# PowerSupply.net
KiCad netlist of a schematic drawn in Altium Designer
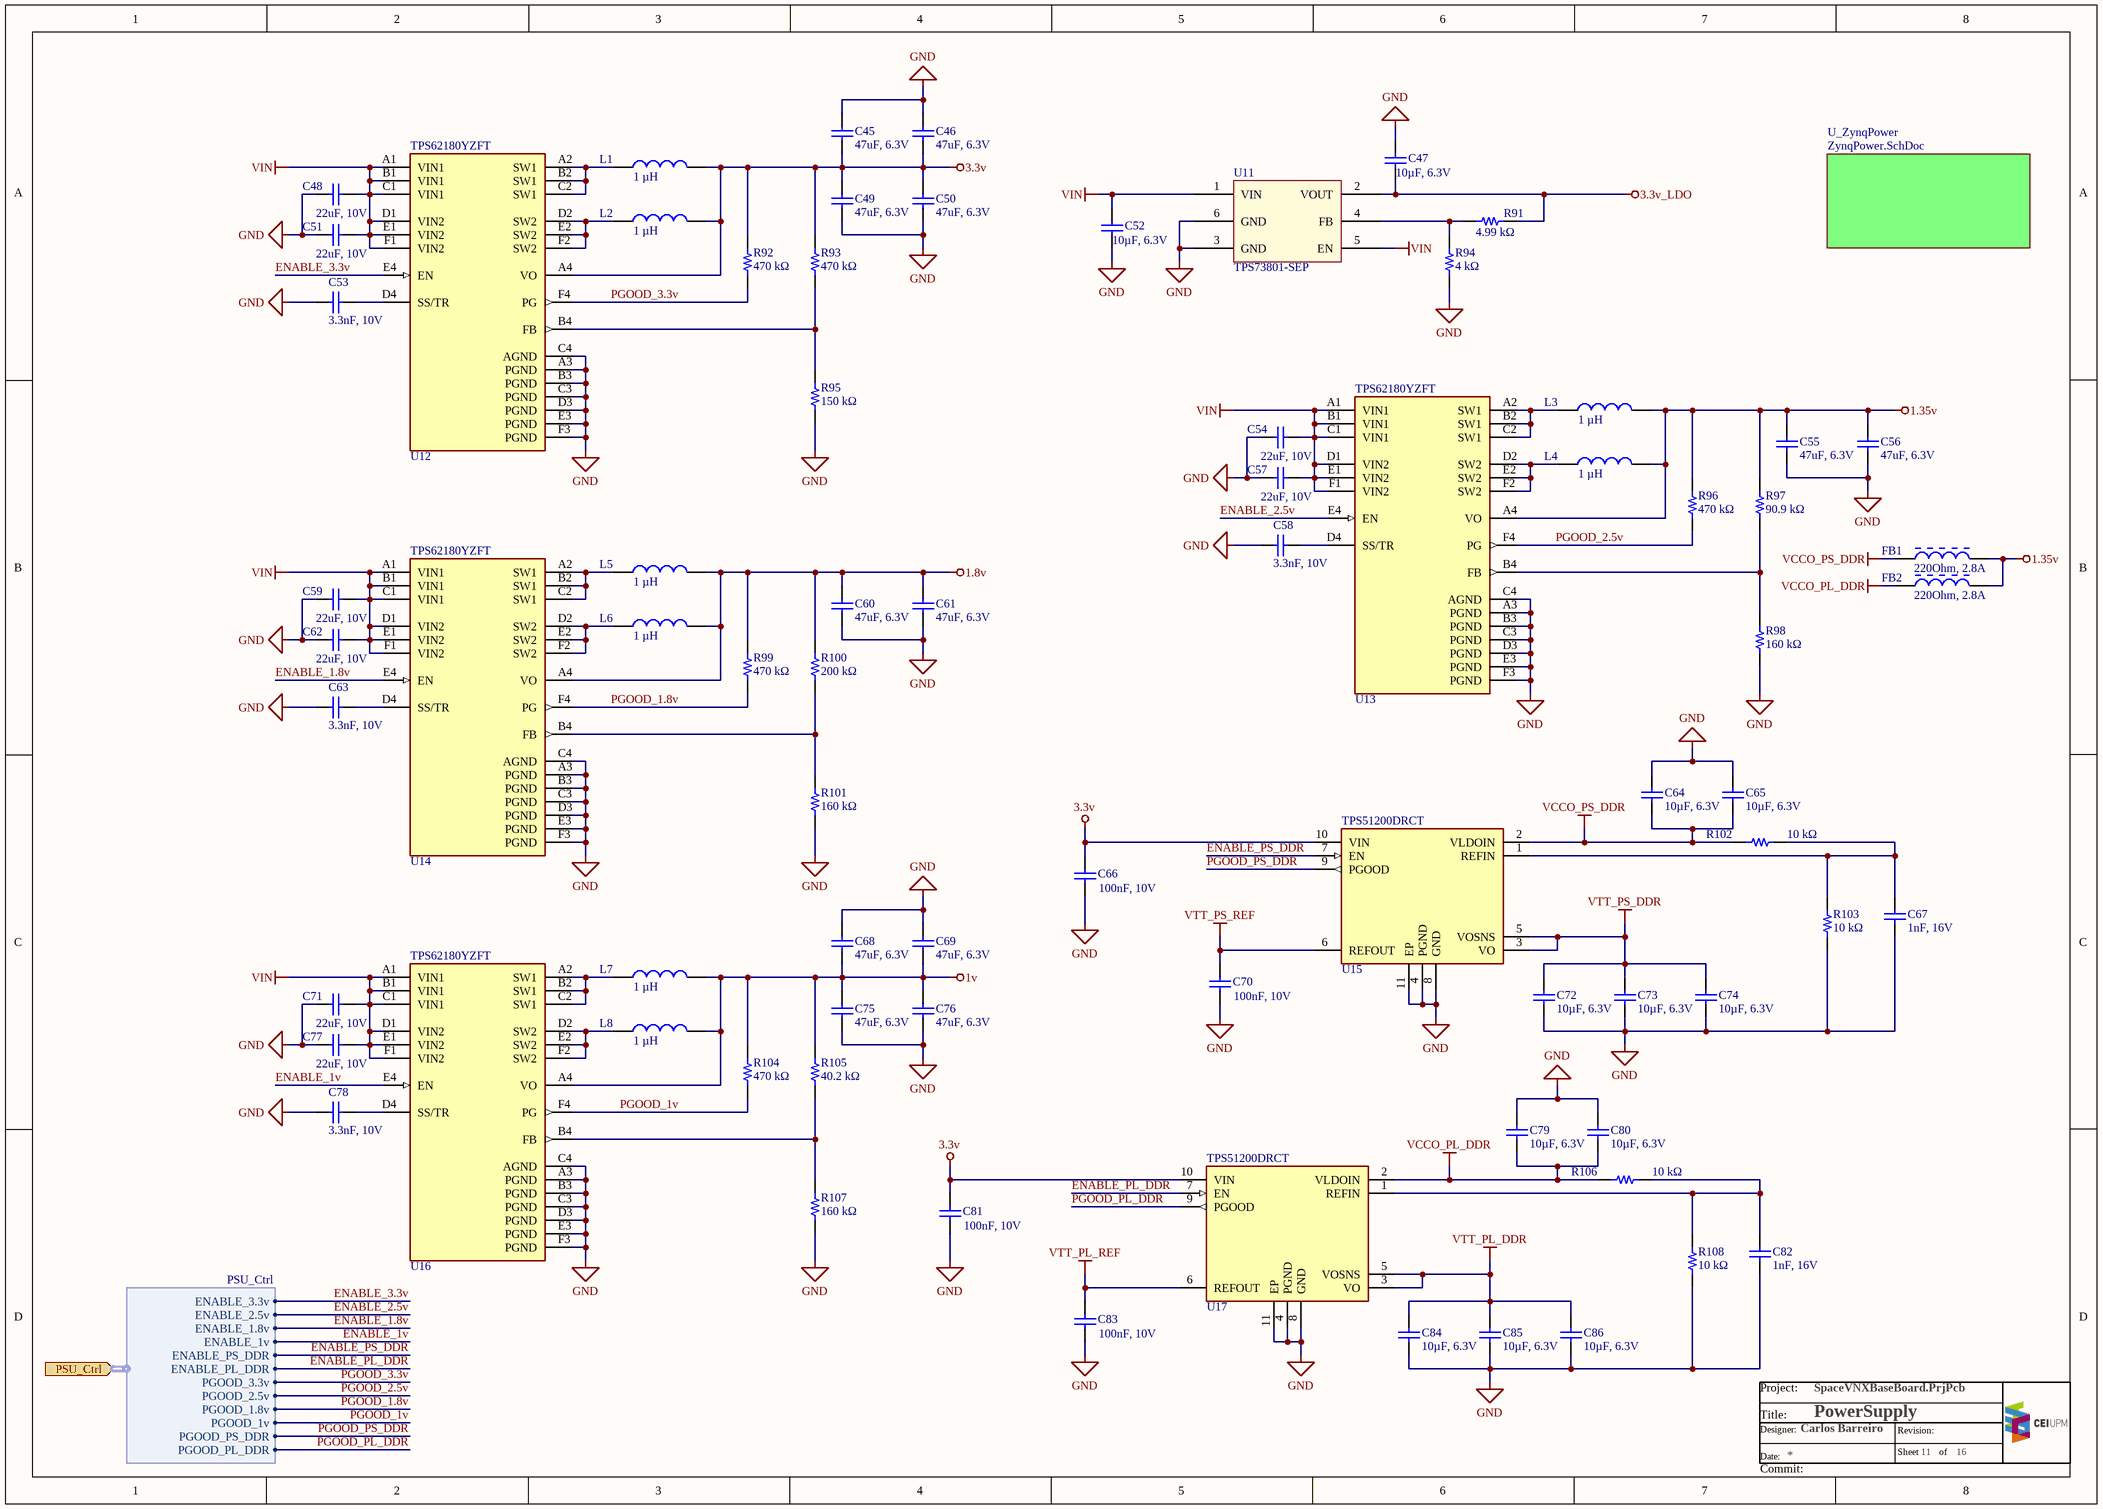
[diagram p0: PowerSupply.SchDoc]

(export (version "E")
  (design (tool "Eeschema 10.0.6"))
  (components
    (comp (ref "C45")
      (value "47uF, 6.3V")
      (footprint "WURTH_WCAP-CSGP_0805_H=1.25mm")
      (description "WCAP-CSGP Multilayer Ceramic Chip Capacitor, General Purpose, size 0805, X5R, 47uF, 6.3V")
      (fields
        (field (name "MANUFACTURER PART NUMBER") "885012107006")
        (field (name "MANUFACTURER") "Wurth Elektronik")
      )
      (libsource (lib "SpaceVNX") (part "885012107006"))
    )
    (comp (ref "C46")
      (value "47uF, 6.3V")
      (footprint "WURTH_WCAP-CSGP_0805_H=1.25mm")
      (description "WCAP-CSGP Multilayer Ceramic Chip Capacitor, General Purpose, size 0805, X5R, 47uF, 6.3V")
      (fields
        (field (name "MANUFACTURER PART NUMBER") "885012107006")
        (field (name "MANUFACTURER") "Wurth Elektronik")
      )
      (libsource (lib "SpaceVNX") (part "885012107006"))
    )
    (comp (ref "C47")
      (value "10µF, 6.3V")
      (footprint "WURTH_WCAP-CSGP_0402")
      (description "WCAP-CSGP Multilayer Ceramic Chip Capacitor, General Purpose, size 0402, X5R, 10uF, 6.3V")
      (fields
        (field (name "MANUFACTURER PART NUMBER") "885012105020")
        (field (name "MANUFACTURER") "Wurth Elektronik")
      )
      (libsource (lib "SpaceVNX") (part "885012105020"))
    )
    (comp (ref "C48")
      (value "22uF, 10V")
      (footprint "WURTH_WCAP-CSGP_0805_H=1.25mm")
      (description "WCAP-CSGP Multilayer Ceramic Chip Capacitor, General Purpose, size 0805, X5R, 22uF, 10V")
      (fields
        (field (name "MANUFACTURER PART NUMBER") "885012107011")
        (field (name "MANUFACTURER") "Wurth Elektronik")
      )
      (libsource (lib "SpaceVNX") (part "885012107011"))
    )
    (comp (ref "C49")
      (value "47uF, 6.3V")
      (footprint "WURTH_WCAP-CSGP_0805_H=1.25mm")
      (description "WCAP-CSGP Multilayer Ceramic Chip Capacitor, General Purpose, size 0805, X5R, 47uF, 6.3V")
      (fields
        (field (name "MANUFACTURER PART NUMBER") "885012107006")
        (field (name "MANUFACTURER") "Wurth Elektronik")
      )
      (libsource (lib "SpaceVNX") (part "885012107006"))
    )
    (comp (ref "C50")
      (value "47uF, 6.3V")
      (footprint "WURTH_WCAP-CSGP_0805_H=1.25mm")
      (description "WCAP-CSGP Multilayer Ceramic Chip Capacitor, General Purpose, size 0805, X5R, 47uF, 6.3V")
      (fields
        (field (name "MANUFACTURER PART NUMBER") "885012107006")
        (field (name "MANUFACTURER") "Wurth Elektronik")
      )
      (libsource (lib "SpaceVNX") (part "885012107006"))
    )
    (comp (ref "C51")
      (value "22uF, 10V")
      (footprint "WURTH_WCAP-CSGP_0805_H=1.25mm")
      (description "WCAP-CSGP Multilayer Ceramic Chip Capacitor, General Purpose, size 0805, X5R, 22uF, 10V")
      (fields
        (field (name "MANUFACTURER PART NUMBER") "885012107011")
        (field (name "MANUFACTURER") "Wurth Elektronik")
      )
      (libsource (lib "SpaceVNX") (part "885012107011"))
    )
    (comp (ref "C52")
      (value "10µF, 6.3V")
      (footprint "WURTH_WCAP-CSGP_0402")
      (description "WCAP-CSGP Multilayer Ceramic Chip Capacitor, General Purpose, size 0402, X5R, 10uF, 6.3V")
      (fields
        (field (name "MANUFACTURER PART NUMBER") "885012105020")
        (field (name "MANUFACTURER") "Wurth Elektronik")
      )
      (libsource (lib "SpaceVNX") (part "885012105020"))
    )
    (comp (ref "C53")
      (value "3.3nF, 10V")
      (footprint "WURTH_WCAP-CSGP_0402")
      (description "WCAP-CSGP Multilayer Ceramic Chip Capacitor, General Purpose, size 0402, X7R, 3.3nF, 10V")
      (fields
        (field (name "MANUFACTURER PART NUMBER") "885012205009")
        (field (name "MANUFACTURER") "Wurth Elektronik")
      )
      (libsource (lib "SpaceVNX") (part "885012205009"))
    )
    (comp (ref "C54")
      (value "22uF, 10V")
      (footprint "WURTH_WCAP-CSGP_0805_H=1.25mm")
      (description "WCAP-CSGP Multilayer Ceramic Chip Capacitor, General Purpose, size 0805, X5R, 22uF, 10V")
      (fields
        (field (name "MANUFACTURER PART NUMBER") "885012107011")
        (field (name "MANUFACTURER") "Wurth Elektronik")
      )
      (libsource (lib "SpaceVNX") (part "885012107011"))
    )
    (comp (ref "C55")
      (value "47uF, 6.3V")
      (footprint "WURTH_WCAP-CSGP_0805_H=1.25mm")
      (description "WCAP-CSGP Multilayer Ceramic Chip Capacitor, General Purpose, size 0805, X5R, 47uF, 6.3V")
      (fields
        (field (name "MANUFACTURER PART NUMBER") "885012107006")
        (field (name "MANUFACTURER") "Wurth Elektronik")
      )
      (libsource (lib "SpaceVNX") (part "885012107006"))
    )
    (comp (ref "C56")
      (value "47uF, 6.3V")
      (footprint "WURTH_WCAP-CSGP_0805_H=1.25mm")
      (description "WCAP-CSGP Multilayer Ceramic Chip Capacitor, General Purpose, size 0805, X5R, 47uF, 6.3V")
      (fields
        (field (name "MANUFACTURER PART NUMBER") "885012107006")
        (field (name "MANUFACTURER") "Wurth Elektronik")
      )
      (libsource (lib "SpaceVNX") (part "885012107006"))
    )
    (comp (ref "C57")
      (value "22uF, 10V")
      (footprint "WURTH_WCAP-CSGP_0805_H=1.25mm")
      (description "WCAP-CSGP Multilayer Ceramic Chip Capacitor, General Purpose, size 0805, X5R, 22uF, 10V")
      (fields
        (field (name "MANUFACTURER PART NUMBER") "885012107011")
        (field (name "MANUFACTURER") "Wurth Elektronik")
      )
      (libsource (lib "SpaceVNX") (part "885012107011"))
    )
    (comp (ref "C58")
      (value "3.3nF, 10V")
      (footprint "WURTH_WCAP-CSGP_0402")
      (description "WCAP-CSGP Multilayer Ceramic Chip Capacitor, General Purpose, size 0402, X7R, 3.3nF, 10V")
      (fields
        (field (name "MANUFACTURER PART NUMBER") "885012205009")
        (field (name "MANUFACTURER") "Wurth Elektronik")
      )
      (libsource (lib "SpaceVNX") (part "885012205009"))
    )
    (comp (ref "C59")
      (value "22uF, 10V")
      (footprint "WURTH_WCAP-CSGP_0805_H=1.25mm")
      (description "WCAP-CSGP Multilayer Ceramic Chip Capacitor, General Purpose, size 0805, X5R, 22uF, 10V")
      (fields
        (field (name "MANUFACTURER PART NUMBER") "885012107011")
        (field (name "MANUFACTURER") "Wurth Elektronik")
      )
      (libsource (lib "SpaceVNX") (part "885012107011"))
    )
    (comp (ref "C60")
      (value "47uF, 6.3V")
      (footprint "WURTH_WCAP-CSGP_0805_H=1.25mm")
      (description "WCAP-CSGP Multilayer Ceramic Chip Capacitor, General Purpose, size 0805, X5R, 47uF, 6.3V")
      (fields
        (field (name "MANUFACTURER PART NUMBER") "885012107006")
        (field (name "MANUFACTURER") "Wurth Elektronik")
      )
      (libsource (lib "SpaceVNX") (part "885012107006"))
    )
    (comp (ref "C61")
      (value "47uF, 6.3V")
      (footprint "WURTH_WCAP-CSGP_0805_H=1.25mm")
      (description "WCAP-CSGP Multilayer Ceramic Chip Capacitor, General Purpose, size 0805, X5R, 47uF, 6.3V")
      (fields
        (field (name "MANUFACTURER PART NUMBER") "885012107006")
        (field (name "MANUFACTURER") "Wurth Elektronik")
      )
      (libsource (lib "SpaceVNX") (part "885012107006"))
    )
    (comp (ref "C62")
      (value "22uF, 10V")
      (footprint "WURTH_WCAP-CSGP_0805_H=1.25mm")
      (description "WCAP-CSGP Multilayer Ceramic Chip Capacitor, General Purpose, size 0805, X5R, 22uF, 10V")
      (fields
        (field (name "MANUFACTURER PART NUMBER") "885012107011")
        (field (name "MANUFACTURER") "Wurth Elektronik")
      )
      (libsource (lib "SpaceVNX") (part "885012107011"))
    )
    (comp (ref "C63")
      (value "3.3nF, 10V")
      (footprint "WURTH_WCAP-CSGP_0402")
      (description "WCAP-CSGP Multilayer Ceramic Chip Capacitor, General Purpose, size 0402, X7R, 3.3nF, 10V")
      (fields
        (field (name "MANUFACTURER PART NUMBER") "885012205009")
        (field (name "MANUFACTURER") "Wurth Elektronik")
      )
      (libsource (lib "SpaceVNX") (part "885012205009"))
    )
    (comp (ref "C64")
      (value "10µF, 6.3V")
      (footprint "WURTH_WCAP-CSGP_0402")
      (description "WCAP-CSGP Multilayer Ceramic Chip Capacitor, General Purpose, size 0402, X5R, 10uF, 6.3V")
      (fields
        (field (name "MANUFACTURER PART NUMBER") "885012105020")
        (field (name "MANUFACTURER") "Wurth Elektronik")
      )
      (libsource (lib "SpaceVNX") (part "885012105020"))
    )
    (comp (ref "C65")
      (value "10µF, 6.3V")
      (footprint "WURTH_WCAP-CSGP_0402")
      (description "WCAP-CSGP Multilayer Ceramic Chip Capacitor, General Purpose, size 0402, X5R, 10uF, 6.3V")
      (fields
        (field (name "MANUFACTURER PART NUMBER") "885012105020")
        (field (name "MANUFACTURER") "Wurth Elektronik")
      )
      (libsource (lib "SpaceVNX") (part "885012105020"))
    )
    (comp (ref "C66")
      (value "100nF, 10V")
      (footprint "WURTH_WCAP-CSGP_0402")
      (description "WCAP-CSGP Multilayer Ceramic Chip Capacitor, General Purpose, size 0402, X7R, 100nF, 10V")
      (fields
        (field (name "MANUFACTURER PART NUMBER") "885012205018")
        (field (name "MANUFACTURER") "Wurth Elektronik")
      )
      (libsource (lib "SpaceVNX") (part "885012205018"))
    )
    (comp (ref "C67")
      (value "1nF, 16V")
      (footprint "WURTH_WCAP-CSGP_0402")
      (description "WCAP-CSGP Multilayer Ceramic Chip Capacitor, General Purpose, size 0402, X7R, 1nF, 16V")
      (fields
        (field (name "MANUFACTURER PART NUMBER") "885012205025")
        (field (name "MANUFACTURER") "Wurth Elektronik")
      )
      (libsource (lib "SpaceVNX") (part "885012205025"))
    )
    (comp (ref "C68")
      (value "47uF, 6.3V")
      (footprint "WURTH_WCAP-CSGP_0805_H=1.25mm")
      (description "WCAP-CSGP Multilayer Ceramic Chip Capacitor, General Purpose, size 0805, X5R, 47uF, 6.3V")
      (fields
        (field (name "MANUFACTURER PART NUMBER") "885012107006")
        (field (name "MANUFACTURER") "Wurth Elektronik")
      )
      (libsource (lib "SpaceVNX") (part "885012107006"))
    )
    (comp (ref "C69")
      (value "47uF, 6.3V")
      (footprint "WURTH_WCAP-CSGP_0805_H=1.25mm")
      (description "WCAP-CSGP Multilayer Ceramic Chip Capacitor, General Purpose, size 0805, X5R, 47uF, 6.3V")
      (fields
        (field (name "MANUFACTURER PART NUMBER") "885012107006")
        (field (name "MANUFACTURER") "Wurth Elektronik")
      )
      (libsource (lib "SpaceVNX") (part "885012107006"))
    )
    (comp (ref "C70")
      (value "100nF, 10V")
      (footprint "WURTH_WCAP-CSGP_0402")
      (description "WCAP-CSGP Multilayer Ceramic Chip Capacitor, General Purpose, size 0402, X7R, 100nF, 10V")
      (fields
        (field (name "MANUFACTURER PART NUMBER") "885012205018")
        (field (name "MANUFACTURER") "Wurth Elektronik")
      )
      (libsource (lib "SpaceVNX") (part "885012205018"))
    )
    (comp (ref "C71")
      (value "22uF, 10V")
      (footprint "WURTH_WCAP-CSGP_0805_H=1.25mm")
      (description "WCAP-CSGP Multilayer Ceramic Chip Capacitor, General Purpose, size 0805, X5R, 22uF, 10V")
      (fields
        (field (name "MANUFACTURER PART NUMBER") "885012107011")
        (field (name "MANUFACTURER") "Wurth Elektronik")
      )
      (libsource (lib "SpaceVNX") (part "885012107011"))
    )
    (comp (ref "C72")
      (value "10µF, 6.3V")
      (footprint "WURTH_WCAP-CSGP_0402")
      (description "WCAP-CSGP Multilayer Ceramic Chip Capacitor, General Purpose, size 0402, X5R, 10uF, 6.3V")
      (fields
        (field (name "MANUFACTURER PART NUMBER") "885012105020")
        (field (name "MANUFACTURER") "Wurth Elektronik")
      )
      (libsource (lib "SpaceVNX") (part "885012105020"))
    )
    (comp (ref "C73")
      (value "10µF, 6.3V")
      (footprint "WURTH_WCAP-CSGP_0402")
      (description "WCAP-CSGP Multilayer Ceramic Chip Capacitor, General Purpose, size 0402, X5R, 10uF, 6.3V")
      (fields
        (field (name "MANUFACTURER PART NUMBER") "885012105020")
        (field (name "MANUFACTURER") "Wurth Elektronik")
      )
      (libsource (lib "SpaceVNX") (part "885012105020"))
    )
    (comp (ref "C74")
      (value "10µF, 6.3V")
      (footprint "WURTH_WCAP-CSGP_0402")
      (description "WCAP-CSGP Multilayer Ceramic Chip Capacitor, General Purpose, size 0402, X5R, 10uF, 6.3V")
      (fields
        (field (name "MANUFACTURER PART NUMBER") "885012105020")
        (field (name "MANUFACTURER") "Wurth Elektronik")
      )
      (libsource (lib "SpaceVNX") (part "885012105020"))
    )
    (comp (ref "C75")
      (value "47uF, 6.3V")
      (footprint "WURTH_WCAP-CSGP_0805_H=1.25mm")
      (description "WCAP-CSGP Multilayer Ceramic Chip Capacitor, General Purpose, size 0805, X5R, 47uF, 6.3V")
      (fields
        (field (name "MANUFACTURER PART NUMBER") "885012107006")
        (field (name "MANUFACTURER") "Wurth Elektronik")
      )
      (libsource (lib "SpaceVNX") (part "885012107006"))
    )
    (comp (ref "C76")
      (value "47uF, 6.3V")
      (footprint "WURTH_WCAP-CSGP_0805_H=1.25mm")
      (description "WCAP-CSGP Multilayer Ceramic Chip Capacitor, General Purpose, size 0805, X5R, 47uF, 6.3V")
      (fields
        (field (name "MANUFACTURER PART NUMBER") "885012107006")
        (field (name "MANUFACTURER") "Wurth Elektronik")
      )
      (libsource (lib "SpaceVNX") (part "885012107006"))
    )
    (comp (ref "C77")
      (value "22uF, 10V")
      (footprint "WURTH_WCAP-CSGP_0805_H=1.25mm")
      (description "WCAP-CSGP Multilayer Ceramic Chip Capacitor, General Purpose, size 0805, X5R, 22uF, 10V")
      (fields
        (field (name "MANUFACTURER PART NUMBER") "885012107011")
        (field (name "MANUFACTURER") "Wurth Elektronik")
      )
      (libsource (lib "SpaceVNX") (part "885012107011"))
    )
    (comp (ref "C78")
      (value "3.3nF, 10V")
      (footprint "WURTH_WCAP-CSGP_0402")
      (description "WCAP-CSGP Multilayer Ceramic Chip Capacitor, General Purpose, size 0402, X7R, 3.3nF, 10V")
      (fields
        (field (name "MANUFACTURER PART NUMBER") "885012205009")
        (field (name "MANUFACTURER") "Wurth Elektronik")
      )
      (libsource (lib "SpaceVNX") (part "885012205009"))
    )
    (comp (ref "C79")
      (value "10µF, 6.3V")
      (footprint "WURTH_WCAP-CSGP_0402")
      (description "WCAP-CSGP Multilayer Ceramic Chip Capacitor, General Purpose, size 0402, X5R, 10uF, 6.3V")
      (fields
        (field (name "MANUFACTURER PART NUMBER") "885012105020")
        (field (name "MANUFACTURER") "Wurth Elektronik")
      )
      (libsource (lib "SpaceVNX") (part "885012105020"))
    )
    (comp (ref "C80")
      (value "10µF, 6.3V")
      (footprint "WURTH_WCAP-CSGP_0402")
      (description "WCAP-CSGP Multilayer Ceramic Chip Capacitor, General Purpose, size 0402, X5R, 10uF, 6.3V")
      (fields
        (field (name "MANUFACTURER PART NUMBER") "885012105020")
        (field (name "MANUFACTURER") "Wurth Elektronik")
      )
      (libsource (lib "SpaceVNX") (part "885012105020"))
    )
    (comp (ref "C81")
      (value "100nF, 10V")
      (footprint "WURTH_WCAP-CSGP_0402")
      (description "WCAP-CSGP Multilayer Ceramic Chip Capacitor, General Purpose, size 0402, X7R, 100nF, 10V")
      (fields
        (field (name "MANUFACTURER PART NUMBER") "885012205018")
        (field (name "MANUFACTURER") "Wurth Elektronik")
      )
      (libsource (lib "SpaceVNX") (part "885012205018"))
    )
    (comp (ref "C82")
      (value "1nF, 16V")
      (footprint "WURTH_WCAP-CSGP_0402")
      (description "WCAP-CSGP Multilayer Ceramic Chip Capacitor, General Purpose, size 0402, X7R, 1nF, 16V")
      (fields
        (field (name "MANUFACTURER PART NUMBER") "885012205025")
        (field (name "MANUFACTURER") "Wurth Elektronik")
      )
      (libsource (lib "SpaceVNX") (part "885012205025"))
    )
    (comp (ref "C83")
      (value "100nF, 10V")
      (footprint "WURTH_WCAP-CSGP_0402")
      (description "WCAP-CSGP Multilayer Ceramic Chip Capacitor, General Purpose, size 0402, X7R, 100nF, 10V")
      (fields
        (field (name "MANUFACTURER PART NUMBER") "885012205018")
        (field (name "MANUFACTURER") "Wurth Elektronik")
      )
      (libsource (lib "SpaceVNX") (part "885012205018"))
    )
    (comp (ref "C84")
      (value "10µF, 6.3V")
      (footprint "WURTH_WCAP-CSGP_0402")
      (description "WCAP-CSGP Multilayer Ceramic Chip Capacitor, General Purpose, size 0402, X5R, 10uF, 6.3V")
      (fields
        (field (name "MANUFACTURER PART NUMBER") "885012105020")
        (field (name "MANUFACTURER") "Wurth Elektronik")
      )
      (libsource (lib "SpaceVNX") (part "885012105020"))
    )
    (comp (ref "C85")
      (value "10µF, 6.3V")
      (footprint "WURTH_WCAP-CSGP_0402")
      (description "WCAP-CSGP Multilayer Ceramic Chip Capacitor, General Purpose, size 0402, X5R, 10uF, 6.3V")
      (fields
        (field (name "MANUFACTURER PART NUMBER") "885012105020")
        (field (name "MANUFACTURER") "Wurth Elektronik")
      )
      (libsource (lib "SpaceVNX") (part "885012105020"))
    )
    (comp (ref "C86")
      (value "10µF, 6.3V")
      (footprint "WURTH_WCAP-CSGP_0402")
      (description "WCAP-CSGP Multilayer Ceramic Chip Capacitor, General Purpose, size 0402, X5R, 10uF, 6.3V")
      (fields
        (field (name "MANUFACTURER PART NUMBER") "885012105020")
        (field (name "MANUFACTURER") "Wurth Elektronik")
      )
      (libsource (lib "SpaceVNX") (part "885012105020"))
    )
    (comp (ref "FB1")
      (value "220Ohm, 2.8A")
      (footprint "WURTH-CBF_0805")
      (description "WE-CBF SMT EMI Suppression Ferrite Bead, size 0805, 220Ohm, 2.8A")
      (fields
        (field (name "MANUFACTURER PART NUMBER") "742792034")
        (field (name "MANUFACTURER") "Wurth Elektronik")
      )
      (libsource (lib "SpaceVNX") (part "742792034"))
    )
    (comp (ref "FB2")
      (value "220Ohm, 2.8A")
      (footprint "WURTH-CBF_0805")
      (description "WE-CBF SMT EMI Suppression Ferrite Bead, size 0805, 220Ohm, 2.8A")
      (fields
        (field (name "MANUFACTURER PART NUMBER") "742792034")
        (field (name "MANUFACTURER") "Wurth Elektronik")
      )
      (libsource (lib "SpaceVNX") (part "742792034"))
    )
    (comp (ref "L1")
      (value "1 µH")
      (footprint "Murata_LQH2HPN_JR")
      (description "Wire Wound Ferrite Inductor")
      (fields (field (name "MANUFACTURER") "Murata"))
      (libsource (lib "SpaceVNX") (part "LQH2HPN1R0NJR"))
    )
    (comp (ref "L2")
      (value "1 µH")
      (footprint "Murata_LQH2HPN_JR")
      (description "Wire Wound Ferrite Inductor")
      (fields (field (name "MANUFACTURER") "Murata"))
      (libsource (lib "SpaceVNX") (part "LQH2HPN1R0NJR"))
    )
    (comp (ref "L3")
      (value "1 µH")
      (footprint "Murata_LQH2HPN_JR")
      (description "Wire Wound Ferrite Inductor")
      (fields (field (name "MANUFACTURER") "Murata"))
      (libsource (lib "SpaceVNX") (part "LQH2HPN1R0NJR"))
    )
    (comp (ref "L4")
      (value "1 µH")
      (footprint "Murata_LQH2HPN_JR")
      (description "Wire Wound Ferrite Inductor")
      (fields (field (name "MANUFACTURER") "Murata"))
      (libsource (lib "SpaceVNX") (part "LQH2HPN1R0NJR"))
    )
    (comp (ref "L5")
      (value "1 µH")
      (footprint "Murata_LQH2HPN_JR")
      (description "Wire Wound Ferrite Inductor")
      (fields (field (name "MANUFACTURER") "Murata"))
      (libsource (lib "SpaceVNX") (part "LQH2HPN1R0NJR"))
    )
    (comp (ref "L6")
      (value "1 µH")
      (footprint "Murata_LQH2HPN_JR")
      (description "Wire Wound Ferrite Inductor")
      (fields (field (name "MANUFACTURER") "Murata"))
      (libsource (lib "SpaceVNX") (part "LQH2HPN1R0NJR"))
    )
    (comp (ref "L7")
      (value "1 µH")
      (footprint "Murata_LQH2HPN_JR")
      (description "Wire Wound Ferrite Inductor")
      (fields (field (name "MANUFACTURER") "Murata"))
      (libsource (lib "SpaceVNX") (part "LQH2HPN1R0NJR"))
    )
    (comp (ref "L8")
      (value "1 µH")
      (footprint "Murata_LQH2HPN_JR")
      (description "Wire Wound Ferrite Inductor")
      (fields (field (name "MANUFACTURER") "Murata"))
      (libsource (lib "SpaceVNX") (part "LQH2HPN1R0NJR"))
    )
    (comp (ref "R91")
      (value "4.99 kΩ")
      (footprint "PANASONIC_ERJ2G_0402")
      (description "General Purpose Thick Film Chip Resistors")
      (fields (field (name "MANUFACTURER") "Panasonic"))
      (libsource (lib "SpaceVNX") (part "ERJ2RKF4991X"))
    )
    (comp (ref "R92")
      (value "470 kΩ")
      (footprint "PANASONIC_ERJ2G_0402")
      (description "General Purpose Thick Film Chip Resistors")
      (fields (field (name "MANUFACTURER") "Panasonic"))
      (libsource (lib "SpaceVNX") (part "ERJ2RKF4703X"))
    )
    (comp (ref "R93")
      (value "470 kΩ")
      (footprint "PANASONIC_ERJ2G_0402")
      (description "General Purpose Thick Film Chip Resistors")
      (fields (field (name "MANUFACTURER") "Panasonic"))
      (libsource (lib "SpaceVNX") (part "ERJ2RKF4703X"))
    )
    (comp (ref "R94")
      (value "4 kΩ")
      (footprint "PANASONIC_ERJ2G_0402")
      (description "General Purpose Thick Film Chip Resistors")
      (fields (field (name "MANUFACTURER") "Panasonic"))
      (libsource (lib "SpaceVNX") (part "ERJ2RKF4021X"))
    )
    (comp (ref "R95")
      (value "150 kΩ")
      (footprint "PANASONIC_ERJ2G_0402")
      (description "General Purpose Thick Film Chip Resistors")
      (fields (field (name "MANUFACTURER") "Panasonic"))
      (libsource (lib "SpaceVNX") (part "ERJ2RKF1503X"))
    )
    (comp (ref "R96")
      (value "470 kΩ")
      (footprint "PANASONIC_ERJ2G_0402")
      (description "General Purpose Thick Film Chip Resistors")
      (fields (field (name "MANUFACTURER") "Panasonic"))
      (libsource (lib "SpaceVNX") (part "ERJ2RKF4703X"))
    )
    (comp (ref "R97")
      (value "90.9 kΩ")
      (footprint "PANASONIC_ERJ2G_0402")
      (description "General Purpose Thick Film Chip Resistors")
      (fields (field (name "MANUFACTURER") "Panasonic"))
      (libsource (lib "SpaceVNX") (part "ERJ2RKF9092X"))
    )
    (comp (ref "R98")
      (value "160 kΩ")
      (footprint "PANASONIC_ERJ2G_0402")
      (description "General Purpose Thick Film Chip Resistors")
      (fields (field (name "MANUFACTURER") "Panasonic"))
      (libsource (lib "SpaceVNX") (part "ERJ2RKF1603X"))
    )
    (comp (ref "R99")
      (value "470 kΩ")
      (footprint "PANASONIC_ERJ2G_0402")
      (description "General Purpose Thick Film Chip Resistors")
      (fields (field (name "MANUFACTURER") "Panasonic"))
      (libsource (lib "SpaceVNX") (part "ERJ2RKF4703X"))
    )
    (comp (ref "R100")
      (value "200 kΩ")
      (footprint "PANASONIC_ERJ2G_0402")
      (description "General Purpose Thick Film Chip Resistors")
      (fields (field (name "MANUFACTURER") "Panasonic"))
      (libsource (lib "SpaceVNX") (part "ERJ2RKF2003X"))
    )
    (comp (ref "R101")
      (value "160 kΩ")
      (footprint "PANASONIC_ERJ2G_0402")
      (description "General Purpose Thick Film Chip Resistors")
      (fields (field (name "MANUFACTURER") "Panasonic"))
      (libsource (lib "SpaceVNX") (part "ERJ2RKF1603X"))
    )
    (comp (ref "R102")
      (value "10 kΩ")
      (footprint "PANASONIC_ERJ2G_0402")
      (description "General Purpose Thick Film Chip Resistors")
      (fields (field (name "MANUFACTURER") "Panasonic"))
      (libsource (lib "SpaceVNX") (part "ERJ2RKF1002X"))
    )
    (comp (ref "R103")
      (value "10 kΩ")
      (footprint "PANASONIC_ERJ2G_0402")
      (description "General Purpose Thick Film Chip Resistors")
      (fields (field (name "MANUFACTURER") "Panasonic"))
      (libsource (lib "SpaceVNX") (part "ERJ2RKF1002X"))
    )
    (comp (ref "R104")
      (value "470 kΩ")
      (footprint "PANASONIC_ERJ2G_0402")
      (description "General Purpose Thick Film Chip Resistors")
      (fields (field (name "MANUFACTURER") "Panasonic"))
      (libsource (lib "SpaceVNX") (part "ERJ2RKF4703X"))
    )
    (comp (ref "R105")
      (value "40.2 kΩ")
      (footprint "PANASONIC_ERJ2G_0402")
      (description "General Purpose Thick Film Chip Resistors")
      (fields (field (name "MANUFACTURER") "Panasonic"))
      (libsource (lib "SpaceVNX") (part "ERJ2RKF4022X"))
    )
    (comp (ref "R106")
      (value "10 kΩ")
      (footprint "PANASONIC_ERJ2G_0402")
      (description "General Purpose Thick Film Chip Resistors")
      (fields (field (name "MANUFACTURER") "Panasonic"))
      (libsource (lib "SpaceVNX") (part "ERJ2RKF1002X"))
    )
    (comp (ref "R107")
      (value "160 kΩ")
      (footprint "PANASONIC_ERJ2G_0402")
      (description "General Purpose Thick Film Chip Resistors")
      (fields (field (name "MANUFACTURER") "Panasonic"))
      (libsource (lib "SpaceVNX") (part "ERJ2RKF1603X"))
    )
    (comp (ref "R108")
      (value "10 kΩ")
      (footprint "PANASONIC_ERJ2G_0402")
      (description "General Purpose Thick Film Chip Resistors")
      (fields (field (name "MANUFACTURER") "Panasonic"))
      (libsource (lib "SpaceVNX") (part "ERJ2RKF1002X"))
    )
    (comp (ref "U11")
      (value "TPS73801-SEP")
      (footprint "TEXAS_SOT223DCQ")
      (description "Radiation-hardened, 2.2-V to 20-V, 1-A low-noise adjustable output LDO in Space Enhanced Plastic")
      (libsource (lib "SpaceVNX") (part "TPS73801-SEP"))
    )
    (comp (ref "U12")
      (value "TPS62180YZFT")
      (footprint "TEXAS_DSBGA24")
      (description "TPS6218x 4-V to 15-V, 6-A, 2-Phase Step-Down Converters")
      (libsource (lib "SpaceVNX") (part "TPS62180YZFT"))
    )
    (comp (ref "U13")
      (value "TPS62180YZFT")
      (footprint "TEXAS_DSBGA24")
      (description "TPS6218x 4-V to 15-V, 6-A, 2-Phase Step-Down Converters")
      (libsource (lib "SpaceVNX") (part "TPS62180YZFT"))
    )
    (comp (ref "U14")
      (value "TPS62180YZFT")
      (footprint "TEXAS_DSBGA24")
      (description "TPS6218x 4-V to 15-V, 6-A, 2-Phase Step-Down Converters")
      (libsource (lib "SpaceVNX") (part "TPS62180YZFT"))
    )
    (comp (ref "U15")
      (value "TPS51200DRCT")
      (footprint "TEXAS_VSON10")
      (fields (field (name "MF") "Texas Instruments"))
      (libsource (lib "SpaceVNX") (part "TPS51200DRCT"))
    )
    (comp (ref "U16")
      (value "TPS62180YZFT")
      (footprint "TEXAS_DSBGA24")
      (description "TPS6218x 4-V to 15-V, 6-A, 2-Phase Step-Down Converters")
      (libsource (lib "SpaceVNX") (part "TPS62180YZFT"))
    )
    (comp (ref "U17")
      (value "TPS51200DRCT")
      (footprint "TEXAS_VSON10")
      (fields (field (name "MF") "Texas Instruments"))
      (libsource (lib "SpaceVNX") (part "TPS51200DRCT"))
    )
  )
  (nets
    (net (code "2") (name "/ENABLE_1.8v") (class "Default")
      (node (ref "U14") (pin "E4") (pinfunction "EN_E4") (pintype "input"))
    )
    (net (code "3") (name "/ENABLE_1v") (class "Default")
      (node (ref "U16") (pin "E4") (pinfunction "EN_E4") (pintype "input"))
    )
    (net (code "4") (name "/ENABLE_2.5v") (class "Default")
      (node (ref "U13") (pin "E4") (pinfunction "EN_E4") (pintype "input"))
    )
    (net (code "5") (name "/ENABLE_3.3v") (class "Default")
      (node (ref "U12") (pin "E4") (pinfunction "EN_E4") (pintype "input"))
    )
    (net (code "6") (name "/ENABLE_PL_DDR") (class "Default")
      (node (ref "U17") (pin "7") (pinfunction "EN_7") (pintype "input"))
    )
    (net (code "7") (name "/ENABLE_PS_DDR") (class "Default")
      (node (ref "U15") (pin "7") (pinfunction "EN_7") (pintype "input"))
    )
    (net (code "8") (name "/PGOOD_1.8v") (class "Default")
      (node (ref "R99") (pin "1") (pinfunction "1_1") (pintype "passive"))
      (node (ref "U14") (pin "F4") (pinfunction "PG_F4") (pintype "output"))
    )
    (net (code "9") (name "/PGOOD_1v") (class "Default")
      (node (ref "R104") (pin "1") (pinfunction "1_1") (pintype "passive"))
      (node (ref "U16") (pin "F4") (pinfunction "PG_F4") (pintype "output"))
    )
    (net (code "10") (name "/PGOOD_2.5v") (class "Default")
      (node (ref "R96") (pin "1") (pinfunction "1_1") (pintype "passive"))
      (node (ref "U13") (pin "F4") (pinfunction "PG_F4") (pintype "output"))
    )
    (net (code "11") (name "/PGOOD_3.3v") (class "Default")
      (node (ref "R92") (pin "1") (pinfunction "1_1") (pintype "passive"))
      (node (ref "U12") (pin "F4") (pinfunction "PG_F4") (pintype "output"))
    )
    (net (code "12") (name "/PGOOD_PL_DDR") (class "Default")
      (node (ref "U17") (pin "9") (pinfunction "PGOOD_9") (pintype "output"))
    )
    (net (code "13") (name "/PGOOD_PS_DDR") (class "Default")
      (node (ref "U15") (pin "9") (pinfunction "PGOOD_9") (pintype "output"))
    )
    (net (code "15") (name "1.8v") (class "Default")
      (node (ref "C60") (pin "2") (pinfunction "2_2") (pintype "passive"))
      (node (ref "C61") (pin "2") (pinfunction "2_2") (pintype "passive"))
      (node (ref "L5") (pin "2") (pinfunction "2_2") (pintype "passive"))
      (node (ref "L6") (pin "2") (pinfunction "2_2") (pintype "passive"))
      (node (ref "R100") (pin "2") (pinfunction "2_2") (pintype "passive"))
      (node (ref "R99") (pin "2") (pinfunction "2_2") (pintype "passive"))
      (node (ref "U14") (pin "A4") (pinfunction "VO_A4") (pintype "power_in"))
    )
    (net (code "16") (name "1.35v") (class "Default")
      (node (ref "C55") (pin "2") (pinfunction "2_2") (pintype "passive"))
      (node (ref "C56") (pin "2") (pinfunction "2_2") (pintype "passive"))
      (node (ref "FB1") (pin "2") (pinfunction "2_2") (pintype "passive"))
      (node (ref "FB2") (pin "2") (pinfunction "2_2") (pintype "passive"))
      (node (ref "L3") (pin "2") (pinfunction "2_2") (pintype "passive"))
      (node (ref "L4") (pin "2") (pinfunction "2_2") (pintype "passive"))
      (node (ref "R96") (pin "2") (pinfunction "2_2") (pintype "passive"))
      (node (ref "R97") (pin "2") (pinfunction "2_2") (pintype "passive"))
      (node (ref "U13") (pin "A4") (pinfunction "VO_A4") (pintype "power_in"))
    )
    (net (code "17") (name "1v") (class "Default")
      (node (ref "C68") (pin "1") (pinfunction "1_1") (pintype "passive"))
      (node (ref "C69") (pin "1") (pinfunction "1_1") (pintype "passive"))
      (node (ref "C75") (pin "2") (pinfunction "2_2") (pintype "passive"))
      (node (ref "C76") (pin "2") (pinfunction "2_2") (pintype "passive"))
      (node (ref "L7") (pin "2") (pinfunction "2_2") (pintype "passive"))
      (node (ref "L8") (pin "2") (pinfunction "2_2") (pintype "passive"))
      (node (ref "R104") (pin "2") (pinfunction "2_2") (pintype "passive"))
      (node (ref "R105") (pin "2") (pinfunction "2_2") (pintype "passive"))
      (node (ref "U16") (pin "A4") (pinfunction "VO_A4") (pintype "power_in"))
    )
    (net (code "18") (name "3.3v") (class "Default")
      (node (ref "C45") (pin "1") (pinfunction "1_1") (pintype "passive"))
      (node (ref "C46") (pin "1") (pinfunction "1_1") (pintype "passive"))
      (node (ref "C49") (pin "2") (pinfunction "2_2") (pintype "passive"))
      (node (ref "C50") (pin "2") (pinfunction "2_2") (pintype "passive"))
      (node (ref "C66") (pin "2") (pinfunction "2_2") (pintype "passive"))
      (node (ref "C81") (pin "2") (pinfunction "2_2") (pintype "passive"))
      (node (ref "L1") (pin "2") (pinfunction "2_2") (pintype "passive"))
      (node (ref "L2") (pin "2") (pinfunction "2_2") (pintype "passive"))
      (node (ref "R92") (pin "2") (pinfunction "2_2") (pintype "passive"))
      (node (ref "R93") (pin "2") (pinfunction "2_2") (pintype "passive"))
      (node (ref "U12") (pin "A4") (pinfunction "VO_A4") (pintype "power_in"))
      (node (ref "U15") (pin "10") (pinfunction "VIN_10") (pintype "passive"))
      (node (ref "U17") (pin "10") (pinfunction "VIN_10") (pintype "passive"))
    )
    (net (code "19") (name "3.3v_LDO") (class "Default")
      (node (ref "C47") (pin "1") (pinfunction "1_1") (pintype "passive"))
      (node (ref "R91") (pin "2") (pinfunction "2_2") (pintype "passive"))
      (node (ref "U11") (pin "2") (pinfunction "VOUT_2") (pintype "passive"))
    )
    (net (code "20") (name "GND") (class "Default")
      (node (ref "C45") (pin "2") (pinfunction "2_2") (pintype "passive"))
      (node (ref "C46") (pin "2") (pinfunction "2_2") (pintype "passive"))
      (node (ref "C47") (pin "2") (pinfunction "2_2") (pintype "passive"))
      (node (ref "C48") (pin "2") (pinfunction "2_2") (pintype "passive"))
      (node (ref "C49") (pin "1") (pinfunction "1_1") (pintype "passive"))
      (node (ref "C50") (pin "1") (pinfunction "1_1") (pintype "passive"))
      (node (ref "C51") (pin "2") (pinfunction "2_2") (pintype "passive"))
      (node (ref "C52") (pin "1") (pinfunction "1_1") (pintype "passive"))
      (node (ref "C53") (pin "1") (pinfunction "1_1") (pintype "passive"))
      (node (ref "C54") (pin "2") (pinfunction "2_2") (pintype "passive"))
      (node (ref "C55") (pin "1") (pinfunction "1_1") (pintype "passive"))
      (node (ref "C56") (pin "1") (pinfunction "1_1") (pintype "passive"))
      (node (ref "C57") (pin "2") (pinfunction "2_2") (pintype "passive"))
      (node (ref "C58") (pin "1") (pinfunction "1_1") (pintype "passive"))
      (node (ref "C59") (pin "2") (pinfunction "2_2") (pintype "passive"))
      (node (ref "C60") (pin "1") (pinfunction "1_1") (pintype "passive"))
      (node (ref "C61") (pin "1") (pinfunction "1_1") (pintype "passive"))
      (node (ref "C62") (pin "2") (pinfunction "2_2") (pintype "passive"))
      (node (ref "C63") (pin "1") (pinfunction "1_1") (pintype "passive"))
      (node (ref "C64") (pin "1") (pinfunction "1_1") (pintype "passive"))
      (node (ref "C65") (pin "1") (pinfunction "1_1") (pintype "passive"))
      (node (ref "C66") (pin "1") (pinfunction "1_1") (pintype "passive"))
      (node (ref "C67") (pin "2") (pinfunction "2_2") (pintype "passive"))
      (node (ref "C68") (pin "2") (pinfunction "2_2") (pintype "passive"))
      (node (ref "C69") (pin "2") (pinfunction "2_2") (pintype "passive"))
      (node (ref "C70") (pin "1") (pinfunction "1_1") (pintype "passive"))
      (node (ref "C71") (pin "2") (pinfunction "2_2") (pintype "passive"))
      (node (ref "C72") (pin "1") (pinfunction "1_1") (pintype "passive"))
      (node (ref "C73") (pin "1") (pinfunction "1_1") (pintype "passive"))
      (node (ref "C74") (pin "1") (pinfunction "1_1") (pintype "passive"))
      (node (ref "C75") (pin "1") (pinfunction "1_1") (pintype "passive"))
      (node (ref "C76") (pin "1") (pinfunction "1_1") (pintype "passive"))
      (node (ref "C77") (pin "2") (pinfunction "2_2") (pintype "passive"))
      (node (ref "C78") (pin "1") (pinfunction "1_1") (pintype "passive"))
      (node (ref "C79") (pin "1") (pinfunction "1_1") (pintype "passive"))
      (node (ref "C80") (pin "1") (pinfunction "1_1") (pintype "passive"))
      (node (ref "C81") (pin "1") (pinfunction "1_1") (pintype "passive"))
      (node (ref "C82") (pin "2") (pinfunction "2_2") (pintype "passive"))
      (node (ref "C83") (pin "1") (pinfunction "1_1") (pintype "passive"))
      (node (ref "C84") (pin "1") (pinfunction "1_1") (pintype "passive"))
      (node (ref "C85") (pin "1") (pinfunction "1_1") (pintype "passive"))
      (node (ref "C86") (pin "1") (pinfunction "1_1") (pintype "passive"))
      (node (ref "R101") (pin "1") (pinfunction "1_1") (pintype "passive"))
      (node (ref "R103") (pin "1") (pinfunction "1_1") (pintype "passive"))
      (node (ref "R107") (pin "1") (pinfunction "1_1") (pintype "passive"))
      (node (ref "R108") (pin "1") (pinfunction "1_1") (pintype "passive"))
      (node (ref "R94") (pin "2") (pinfunction "2_2") (pintype "passive"))
      (node (ref "R95") (pin "1") (pinfunction "1_1") (pintype "passive"))
      (node (ref "R98") (pin "1") (pinfunction "1_1") (pintype "passive"))
      (node (ref "U11") (pin "3") (pinfunction "GND_3") (pintype "passive"))
      (node (ref "U11") (pin "6") (pinfunction "GND_6") (pintype "passive"))
      (node (ref "U12") (pin "A3") (pinfunction "PGND_A3") (pintype "power_in"))
      (node (ref "U12") (pin "B3") (pinfunction "PGND_B3") (pintype "power_in"))
      (node (ref "U12") (pin "C3") (pinfunction "PGND_C3") (pintype "power_in"))
      (node (ref "U12") (pin "C4") (pinfunction "AGND_C4") (pintype "power_in"))
      (node (ref "U12") (pin "D3") (pinfunction "PGND_D3") (pintype "power_in"))
      (node (ref "U12") (pin "E3") (pinfunction "PGND_E3") (pintype "power_in"))
      (node (ref "U12") (pin "F3") (pinfunction "PGND_F3") (pintype "power_in"))
      (node (ref "U13") (pin "A3") (pinfunction "PGND_A3") (pintype "power_in"))
      (node (ref "U13") (pin "B3") (pinfunction "PGND_B3") (pintype "power_in"))
      (node (ref "U13") (pin "C3") (pinfunction "PGND_C3") (pintype "power_in"))
      (node (ref "U13") (pin "C4") (pinfunction "AGND_C4") (pintype "power_in"))
      (node (ref "U13") (pin "D3") (pinfunction "PGND_D3") (pintype "power_in"))
      (node (ref "U13") (pin "E3") (pinfunction "PGND_E3") (pintype "power_in"))
      (node (ref "U13") (pin "F3") (pinfunction "PGND_F3") (pintype "power_in"))
      (node (ref "U14") (pin "A3") (pinfunction "PGND_A3") (pintype "power_in"))
      (node (ref "U14") (pin "B3") (pinfunction "PGND_B3") (pintype "power_in"))
      (node (ref "U14") (pin "C3") (pinfunction "PGND_C3") (pintype "power_in"))
      (node (ref "U14") (pin "C4") (pinfunction "AGND_C4") (pintype "power_in"))
      (node (ref "U14") (pin "D3") (pinfunction "PGND_D3") (pintype "power_in"))
      (node (ref "U14") (pin "E3") (pinfunction "PGND_E3") (pintype "power_in"))
      (node (ref "U14") (pin "F3") (pinfunction "PGND_F3") (pintype "power_in"))
      (node (ref "U15") (pin "11") (pinfunction "EP_11") (pintype "power_in"))
      (node (ref "U15") (pin "4") (pinfunction "PGND_4") (pintype "power_in"))
      (node (ref "U15") (pin "8") (pinfunction "GND_8") (pintype "power_in"))
      (node (ref "U16") (pin "A3") (pinfunction "PGND_A3") (pintype "power_in"))
      (node (ref "U16") (pin "B3") (pinfunction "PGND_B3") (pintype "power_in"))
      (node (ref "U16") (pin "C3") (pinfunction "PGND_C3") (pintype "power_in"))
      (node (ref "U16") (pin "C4") (pinfunction "AGND_C4") (pintype "power_in"))
      (node (ref "U16") (pin "D3") (pinfunction "PGND_D3") (pintype "power_in"))
      (node (ref "U16") (pin "E3") (pinfunction "PGND_E3") (pintype "power_in"))
      (node (ref "U16") (pin "F3") (pinfunction "PGND_F3") (pintype "power_in"))
      (node (ref "U17") (pin "11") (pinfunction "EP_11") (pintype "power_in"))
      (node (ref "U17") (pin "4") (pinfunction "PGND_4") (pintype "power_in"))
      (node (ref "U17") (pin "8") (pinfunction "GND_8") (pintype "power_in"))
    )
    (net (code "21") (name "Net-(L1-Pad1)") (class "Default")
      (node (ref "L1") (pin "1") (pinfunction "1_1") (pintype "passive"))
      (node (ref "U12") (pin "A2") (pinfunction "SW1_A2") (pintype "passive"))
      (node (ref "U12") (pin "B2") (pinfunction "SW1_B2") (pintype "passive"))
      (node (ref "U12") (pin "C2") (pinfunction "SW1_C2") (pintype "passive"))
    )
    (net (code "22") (name "Net-(L2-Pad1)") (class "Default")
      (node (ref "L2") (pin "1") (pinfunction "1_1") (pintype "passive"))
      (node (ref "U12") (pin "D2") (pinfunction "SW2_D2") (pintype "passive"))
      (node (ref "U12") (pin "E2") (pinfunction "SW2_E2") (pintype "passive"))
      (node (ref "U12") (pin "F2") (pinfunction "SW2_F2") (pintype "passive"))
    )
    (net (code "23") (name "Net-(L3-Pad1)") (class "Default")
      (node (ref "L3") (pin "1") (pinfunction "1_1") (pintype "passive"))
      (node (ref "U13") (pin "A2") (pinfunction "SW1_A2") (pintype "passive"))
      (node (ref "U13") (pin "B2") (pinfunction "SW1_B2") (pintype "passive"))
      (node (ref "U13") (pin "C2") (pinfunction "SW1_C2") (pintype "passive"))
    )
    (net (code "24") (name "Net-(L4-Pad1)") (class "Default")
      (node (ref "L4") (pin "1") (pinfunction "1_1") (pintype "passive"))
      (node (ref "U13") (pin "D2") (pinfunction "SW2_D2") (pintype "passive"))
      (node (ref "U13") (pin "E2") (pinfunction "SW2_E2") (pintype "passive"))
      (node (ref "U13") (pin "F2") (pinfunction "SW2_F2") (pintype "passive"))
    )
    (net (code "25") (name "Net-(L5-Pad1)") (class "Default")
      (node (ref "L5") (pin "1") (pinfunction "1_1") (pintype "passive"))
      (node (ref "U14") (pin "A2") (pinfunction "SW1_A2") (pintype "passive"))
      (node (ref "U14") (pin "B2") (pinfunction "SW1_B2") (pintype "passive"))
      (node (ref "U14") (pin "C2") (pinfunction "SW1_C2") (pintype "passive"))
    )
    (net (code "26") (name "Net-(L6-Pad1)") (class "Default")
      (node (ref "L6") (pin "1") (pinfunction "1_1") (pintype "passive"))
      (node (ref "U14") (pin "D2") (pinfunction "SW2_D2") (pintype "passive"))
      (node (ref "U14") (pin "E2") (pinfunction "SW2_E2") (pintype "passive"))
      (node (ref "U14") (pin "F2") (pinfunction "SW2_F2") (pintype "passive"))
    )
    (net (code "27") (name "Net-(L7-Pad1)") (class "Default")
      (node (ref "L7") (pin "1") (pinfunction "1_1") (pintype "passive"))
      (node (ref "U16") (pin "A2") (pinfunction "SW1_A2") (pintype "passive"))
      (node (ref "U16") (pin "B2") (pinfunction "SW1_B2") (pintype "passive"))
      (node (ref "U16") (pin "C2") (pinfunction "SW1_C2") (pintype "passive"))
    )
    (net (code "28") (name "Net-(L8-Pad1)") (class "Default")
      (node (ref "L8") (pin "1") (pinfunction "1_1") (pintype "passive"))
      (node (ref "U16") (pin "D2") (pinfunction "SW2_D2") (pintype "passive"))
      (node (ref "U16") (pin "E2") (pinfunction "SW2_E2") (pintype "passive"))
      (node (ref "U16") (pin "F2") (pinfunction "SW2_F2") (pintype "passive"))
    )
    (net (code "29") (name "Net-(U11-FB)") (class "Default")
      (node (ref "R91") (pin "1") (pinfunction "1_1") (pintype "passive"))
      (node (ref "R94") (pin "1") (pinfunction "1_1") (pintype "passive"))
      (node (ref "U11") (pin "4") (pinfunction "FB_4") (pintype "passive"))
    )
    (net (code "30") (name "Net-(U12-FB)") (class "Default")
      (node (ref "R93") (pin "1") (pinfunction "1_1") (pintype "passive"))
      (node (ref "R95") (pin "2") (pinfunction "2_2") (pintype "passive"))
      (node (ref "U12") (pin "B4") (pinfunction "FB_B4") (pintype "output"))
    )
    (net (code "31") (name "Net-(U12-SS{slash}TR)") (class "Default")
      (node (ref "C53") (pin "2") (pinfunction "2_2") (pintype "passive"))
      (node (ref "U12") (pin "D4") (pinfunction "SS/TR_D4") (pintype "passive"))
    )
    (net (code "32") (name "Net-(U13-FB)") (class "Default")
      (node (ref "R97") (pin "1") (pinfunction "1_1") (pintype "passive"))
      (node (ref "R98") (pin "2") (pinfunction "2_2") (pintype "passive"))
      (node (ref "U13") (pin "B4") (pinfunction "FB_B4") (pintype "output"))
    )
    (net (code "33") (name "Net-(U13-SS{slash}TR)") (class "Default")
      (node (ref "C58") (pin "2") (pinfunction "2_2") (pintype "passive"))
      (node (ref "U13") (pin "D4") (pinfunction "SS/TR_D4") (pintype "passive"))
    )
    (net (code "34") (name "Net-(U14-FB)") (class "Default")
      (node (ref "R100") (pin "1") (pinfunction "1_1") (pintype "passive"))
      (node (ref "R101") (pin "2") (pinfunction "2_2") (pintype "passive"))
      (node (ref "U14") (pin "B4") (pinfunction "FB_B4") (pintype "output"))
    )
    (net (code "35") (name "Net-(U14-SS{slash}TR)") (class "Default")
      (node (ref "C63") (pin "2") (pinfunction "2_2") (pintype "passive"))
      (node (ref "U14") (pin "D4") (pinfunction "SS/TR_D4") (pintype "passive"))
    )
    (net (code "36") (name "Net-(U15-REFIN)") (class "Default")
      (node (ref "C67") (pin "1") (pinfunction "1_1") (pintype "passive"))
      (node (ref "R102") (pin "2") (pinfunction "2_2") (pintype "passive"))
      (node (ref "R103") (pin "2") (pinfunction "2_2") (pintype "passive"))
      (node (ref "U15") (pin "1") (pinfunction "REFIN_1") (pintype "passive"))
    )
    (net (code "37") (name "Net-(U16-FB)") (class "Default")
      (node (ref "R105") (pin "1") (pinfunction "1_1") (pintype "passive"))
      (node (ref "R107") (pin "2") (pinfunction "2_2") (pintype "passive"))
      (node (ref "U16") (pin "B4") (pinfunction "FB_B4") (pintype "output"))
    )
    (net (code "38") (name "Net-(U16-SS{slash}TR)") (class "Default")
      (node (ref "C78") (pin "2") (pinfunction "2_2") (pintype "passive"))
      (node (ref "U16") (pin "D4") (pinfunction "SS/TR_D4") (pintype "passive"))
    )
    (net (code "39") (name "Net-(U17-REFIN)") (class "Default")
      (node (ref "C82") (pin "1") (pinfunction "1_1") (pintype "passive"))
      (node (ref "R106") (pin "2") (pinfunction "2_2") (pintype "passive"))
      (node (ref "R108") (pin "2") (pinfunction "2_2") (pintype "passive"))
      (node (ref "U17") (pin "1") (pinfunction "REFIN_1") (pintype "passive"))
    )
    (net (code "40") (name "VCCO_PL_DDR") (class "Default")
      (node (ref "C79") (pin "2") (pinfunction "2_2") (pintype "passive"))
      (node (ref "C80") (pin "2") (pinfunction "2_2") (pintype "passive"))
      (node (ref "FB2") (pin "1") (pinfunction "1_1") (pintype "passive"))
      (node (ref "R106") (pin "1") (pinfunction "1_1") (pintype "passive"))
      (node (ref "U17") (pin "2") (pinfunction "VLDOIN_2") (pintype "passive"))
    )
    (net (code "41") (name "VCCO_PS_DDR") (class "Default")
      (node (ref "C64") (pin "2") (pinfunction "2_2") (pintype "passive"))
      (node (ref "C65") (pin "2") (pinfunction "2_2") (pintype "passive"))
      (node (ref "FB1") (pin "1") (pinfunction "1_1") (pintype "passive"))
      (node (ref "R102") (pin "1") (pinfunction "1_1") (pintype "passive"))
      (node (ref "U15") (pin "2") (pinfunction "VLDOIN_2") (pintype "passive"))
    )
    (net (code "42") (name "VIN") (class "Default")
      (node (ref "C48") (pin "1") (pinfunction "1_1") (pintype "passive"))
      (node (ref "C51") (pin "1") (pinfunction "1_1") (pintype "passive"))
      (node (ref "C52") (pin "2") (pinfunction "2_2") (pintype "passive"))
      (node (ref "C54") (pin "1") (pinfunction "1_1") (pintype "passive"))
      (node (ref "C57") (pin "1") (pinfunction "1_1") (pintype "passive"))
      (node (ref "C59") (pin "1") (pinfunction "1_1") (pintype "passive"))
      (node (ref "C62") (pin "1") (pinfunction "1_1") (pintype "passive"))
      (node (ref "C71") (pin "1") (pinfunction "1_1") (pintype "passive"))
      (node (ref "C77") (pin "1") (pinfunction "1_1") (pintype "passive"))
      (node (ref "U11") (pin "1") (pinfunction "VIN_1") (pintype "passive"))
      (node (ref "U11") (pin "5") (pinfunction "EN_5") (pintype "passive"))
      (node (ref "U12") (pin "A1") (pinfunction "VIN1_A1") (pintype "power_in"))
      (node (ref "U12") (pin "B1") (pinfunction "VIN1_B1") (pintype "power_in"))
      (node (ref "U12") (pin "C1") (pinfunction "VIN1_C1") (pintype "power_in"))
      (node (ref "U12") (pin "D1") (pinfunction "VIN2_D1") (pintype "power_in"))
      (node (ref "U12") (pin "E1") (pinfunction "VIN2_E1") (pintype "power_in"))
      (node (ref "U12") (pin "F1") (pinfunction "VIN2_F1") (pintype "power_in"))
      (node (ref "U13") (pin "A1") (pinfunction "VIN1_A1") (pintype "power_in"))
      (node (ref "U13") (pin "B1") (pinfunction "VIN1_B1") (pintype "power_in"))
      (node (ref "U13") (pin "C1") (pinfunction "VIN1_C1") (pintype "power_in"))
      (node (ref "U13") (pin "D1") (pinfunction "VIN2_D1") (pintype "power_in"))
      (node (ref "U13") (pin "E1") (pinfunction "VIN2_E1") (pintype "power_in"))
      (node (ref "U13") (pin "F1") (pinfunction "VIN2_F1") (pintype "power_in"))
      (node (ref "U14") (pin "A1") (pinfunction "VIN1_A1") (pintype "power_in"))
      (node (ref "U14") (pin "B1") (pinfunction "VIN1_B1") (pintype "power_in"))
      (node (ref "U14") (pin "C1") (pinfunction "VIN1_C1") (pintype "power_in"))
      (node (ref "U14") (pin "D1") (pinfunction "VIN2_D1") (pintype "power_in"))
      (node (ref "U14") (pin "E1") (pinfunction "VIN2_E1") (pintype "power_in"))
      (node (ref "U14") (pin "F1") (pinfunction "VIN2_F1") (pintype "power_in"))
      (node (ref "U16") (pin "A1") (pinfunction "VIN1_A1") (pintype "power_in"))
      (node (ref "U16") (pin "B1") (pinfunction "VIN1_B1") (pintype "power_in"))
      (node (ref "U16") (pin "C1") (pinfunction "VIN1_C1") (pintype "power_in"))
      (node (ref "U16") (pin "D1") (pinfunction "VIN2_D1") (pintype "power_in"))
      (node (ref "U16") (pin "E1") (pinfunction "VIN2_E1") (pintype "power_in"))
      (node (ref "U16") (pin "F1") (pinfunction "VIN2_F1") (pintype "power_in"))
    )
    (net (code "43") (name "VTT_PL_DDR") (class "Default")
      (node (ref "C84") (pin "2") (pinfunction "2_2") (pintype "passive"))
      (node (ref "C85") (pin "2") (pinfunction "2_2") (pintype "passive"))
      (node (ref "C86") (pin "2") (pinfunction "2_2") (pintype "passive"))
      (node (ref "U17") (pin "3") (pinfunction "VO_3") (pintype "passive"))
      (node (ref "U17") (pin "5") (pinfunction "VOSNS_5") (pintype "passive"))
    )
    (net (code "44") (name "VTT_PL_REF") (class "Default")
      (node (ref "C83") (pin "2") (pinfunction "2_2") (pintype "passive"))
      (node (ref "U17") (pin "6") (pinfunction "REFOUT_6") (pintype "passive"))
    )
    (net (code "45") (name "VTT_PS_DDR") (class "Default")
      (node (ref "C72") (pin "2") (pinfunction "2_2") (pintype "passive"))
      (node (ref "C73") (pin "2") (pinfunction "2_2") (pintype "passive"))
      (node (ref "C74") (pin "2") (pinfunction "2_2") (pintype "passive"))
      (node (ref "U15") (pin "3") (pinfunction "VO_3") (pintype "passive"))
      (node (ref "U15") (pin "5") (pinfunction "VOSNS_5") (pintype "passive"))
    )
    (net (code "46") (name "VTT_PS_REF") (class "Default")
      (node (ref "C70") (pin "2") (pinfunction "2_2") (pintype "passive"))
      (node (ref "U15") (pin "6") (pinfunction "REFOUT_6") (pintype "passive"))
    )
  )
)
